# PCIe_UART_Bridge.net
KiCad netlist of a schematic drawn in Altium Designer
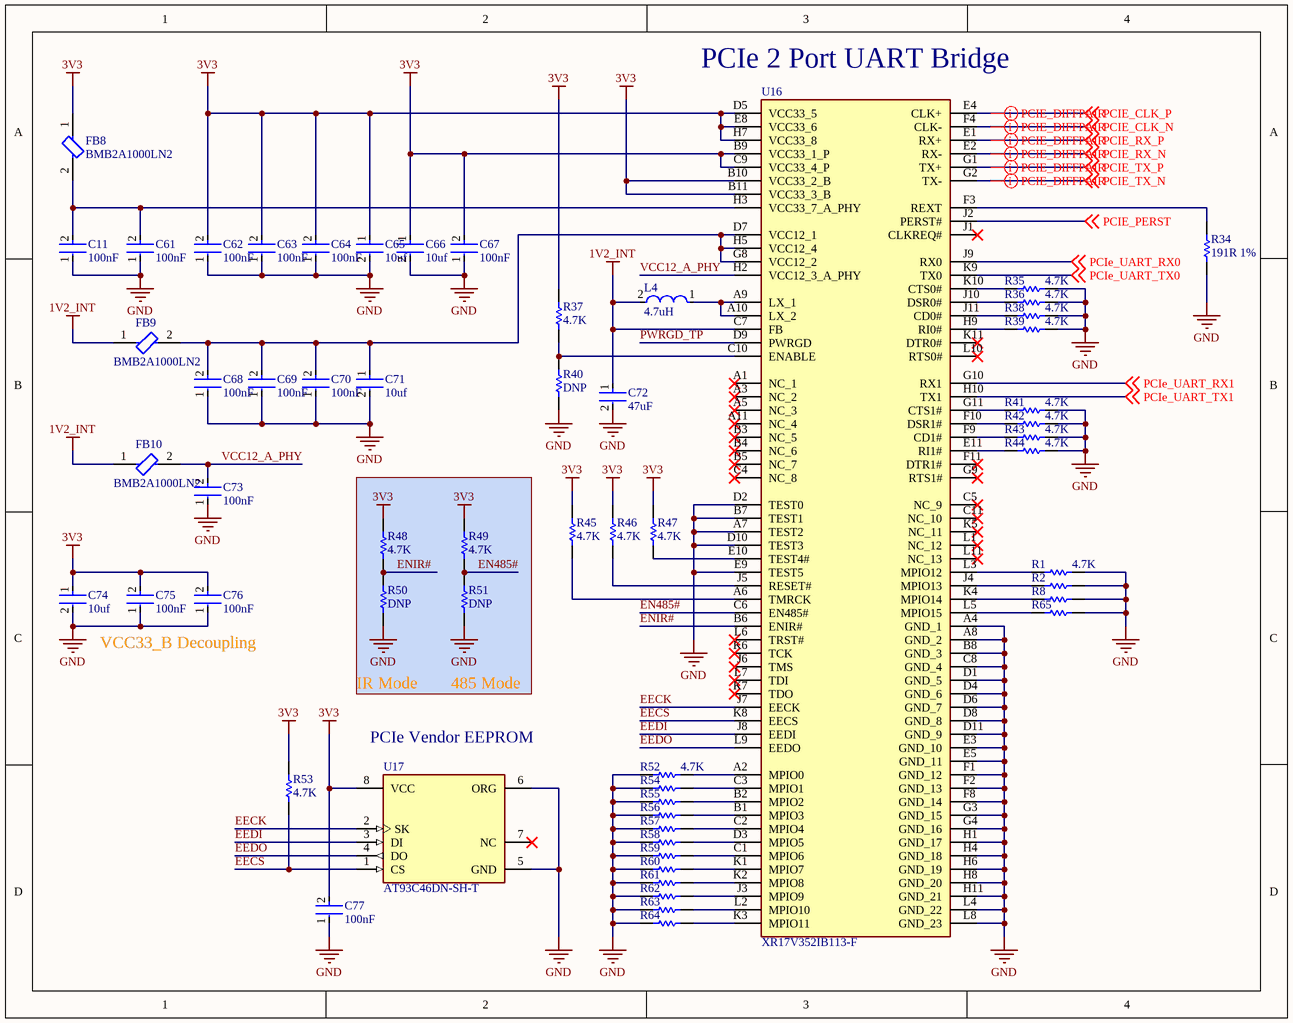
[diagram p0: PCIe_UART_Bridge.SchDoc]

(export (version "E")
  (design (tool "Eeschema 10.0.6"))
  (components
    (comp (ref "C11")
      (value "100nF")
      (footprint "FP-GRM15-MFG")
      (description "CAP CER 0.1UF 16V X7R 0402")
      (fields (field (name "MANUFACTURER PART NUMBER") "GRM155R71C104KA88D") (field (name "TOLERANCE") "10%"))
      (libsource (lib "Altium Content Vault") (part "236180d848d6139a670b325ea6854c9"))
    )
    (comp (ref "C61")
      (value "100nF")
      (footprint "FP-GRM15-MFG")
      (description "CAP CER 0.1UF 16V X7R 0402")
      (fields (field (name "MANUFACTURER PART NUMBER") "GRM155R71C104KA88D") (field (name "TOLERANCE") "10%"))
      (libsource (lib "Altium Content Vault") (part "236180d848d6139a670b325ea6854c9"))
    )
    (comp (ref "C62")
      (value "100nF")
      (footprint "FP-GRM15-MFG")
      (description "CAP CER 0.1UF 16V X7R 0402")
      (fields (field (name "MANUFACTURER PART NUMBER") "GRM155R71C104KA88D") (field (name "TOLERANCE") "10%"))
      (libsource (lib "Altium Content Vault") (part "236180d848d6139a670b325ea6854c9"))
    )
    (comp (ref "C63")
      (value "100nF")
      (footprint "FP-GRM15-MFG")
      (description "CAP CER 0.1UF 16V X7R 0402")
      (fields (field (name "MANUFACTURER PART NUMBER") "GRM155R71C104KA88D") (field (name "TOLERANCE") "10%"))
      (libsource (lib "Altium Content Vault") (part "236180d848d6139a670b325ea6854c9"))
    )
    (comp (ref "C64")
      (value "100nF")
      (footprint "FP-GRM15-MFG")
      (description "CAP CER 0.1UF 16V X7R 0402")
      (fields (field (name "MANUFACTURER PART NUMBER") "GRM155R71C104KA88D") (field (name "TOLERANCE") "10%"))
      (libsource (lib "Altium Content Vault") (part "236180d848d6139a670b325ea6854c9"))
    )
    (comp (ref "C65")
      (value "10uf")
      (footprint "FP-GRM188-0_2-IPC_C")
      (description "Chip Multilayer Ceramic Capacitors for General Purpose, 0603, 10uF, X5R, 15%, 20%, 35V")
      (fields (field (name "TOLERANCE") "20%"))
      (libsource (lib "Altium Content Vault") (part "11868f565c42a9108669ba33697ecf6"))
    )
    (comp (ref "C66")
      (value "10uf")
      (footprint "FP-GRM188-0_2-IPC_C")
      (description "Chip Multilayer Ceramic Capacitors for General Purpose, 0603, 10uF, X5R, 15%, 20%, 35V")
      (fields (field (name "TOLERANCE") "20%"))
      (libsource (lib "Altium Content Vault") (part "11868f565c42a9108669ba33697ecf6"))
    )
    (comp (ref "C67")
      (value "100nF")
      (footprint "FP-GRM15-MFG")
      (description "CAP CER 0.1UF 16V X7R 0402")
      (fields (field (name "MANUFACTURER PART NUMBER") "GRM155R71C104KA88D") (field (name "TOLERANCE") "10%"))
      (libsource (lib "Altium Content Vault") (part "236180d848d6139a670b325ea6854c9"))
    )
    (comp (ref "C68")
      (value "100nF")
      (footprint "FP-GRM15-MFG")
      (description "CAP CER 0.1UF 16V X7R 0402")
      (fields (field (name "MANUFACTURER PART NUMBER") "GRM155R71C104KA88D") (field (name "TOLERANCE") "10%"))
      (libsource (lib "Altium Content Vault") (part "236180d848d6139a670b325ea6854c9"))
    )
    (comp (ref "C69")
      (value "100nF")
      (footprint "FP-GRM15-MFG")
      (description "CAP CER 0.1UF 16V X7R 0402")
      (fields (field (name "MANUFACTURER PART NUMBER") "GRM155R71C104KA88D") (field (name "TOLERANCE") "10%"))
      (libsource (lib "Altium Content Vault") (part "236180d848d6139a670b325ea6854c9"))
    )
    (comp (ref "C70")
      (value "100nF")
      (footprint "FP-GRM15-MFG")
      (description "CAP CER 0.1UF 16V X7R 0402")
      (fields (field (name "MANUFACTURER PART NUMBER") "GRM155R71C104KA88D") (field (name "TOLERANCE") "10%"))
      (libsource (lib "Altium Content Vault") (part "236180d848d6139a670b325ea6854c9"))
    )
    (comp (ref "C71")
      (value "10uf")
      (footprint "FP-GRM188-0_2-IPC_C")
      (description "Chip Multilayer Ceramic Capacitors for General Purpose, 0603, 10uF, X5R, 15%, 20%, 35V")
      (fields (field (name "TOLERANCE") "20%"))
      (libsource (lib "Altium Content Vault") (part "11868f565c42a9108669ba33697ecf6"))
    )
    (comp (ref "C72")
      (value "47uF")
      (footprint "FP-C2012-125-0_2-IPC_B")
      (description "Multilayer Ceramic Capacitors 47μF ±20% 10V X5R SMD 0805")
      (fields (field (name "VOLTAGE") "10V") (field (name "TOLERANCE") "20%"))
      (libsource (lib "Altium Content Vault") (part "b4654b650e69147ec39a6b967a45e02"))
    )
    (comp (ref "C73")
      (value "100nF")
      (footprint "FP-GRM15-MFG")
      (description "CAP CER 0.1UF 16V X7R 0402")
      (fields (field (name "MANUFACTURER PART NUMBER") "GRM155R71C104KA88D") (field (name "TOLERANCE") "10%"))
      (libsource (lib "Altium Content Vault") (part "236180d848d6139a670b325ea6854c9"))
    )
    (comp (ref "C74")
      (value "10uf")
      (footprint "FP-GRM188-0_2-IPC_C")
      (description "Chip Multilayer Ceramic Capacitors for General Purpose, 0603, 10uF, X5R, 15%, 20%, 35V")
      (fields (field (name "TOLERANCE") "20%"))
      (libsource (lib "Altium Content Vault") (part "11868f565c42a9108669ba33697ecf6"))
    )
    (comp (ref "C75")
      (value "100nF")
      (footprint "FP-GRM15-MFG")
      (description "CAP CER 0.1UF 16V X7R 0402")
      (fields (field (name "MANUFACTURER PART NUMBER") "GRM155R71C104KA88D") (field (name "TOLERANCE") "10%"))
      (libsource (lib "Altium Content Vault") (part "236180d848d6139a670b325ea6854c9"))
    )
    (comp (ref "C76")
      (value "100nF")
      (footprint "FP-GRM15-MFG")
      (description "CAP CER 0.1UF 16V X7R 0402")
      (fields (field (name "MANUFACTURER PART NUMBER") "GRM155R71C104KA88D") (field (name "TOLERANCE") "10%"))
      (libsource (lib "Altium Content Vault") (part "236180d848d6139a670b325ea6854c9"))
    )
    (comp (ref "C77")
      (value "100nF")
      (footprint "FP-GRM15-MFG")
      (description "CAP CER 0.1UF 16V X7R 0402")
      (fields (field (name "MANUFACTURER PART NUMBER") "GRM155R71C104KA88D") (field (name "TOLERANCE") "10%"))
      (libsource (lib "Altium Content Vault") (part "236180d848d6139a670b325ea6854c9"))
    )
    (comp (ref "FB8")
      (value "BMB2A1000LN2")
      (footprint "FP-BMB2A1000LN2-IPC_C")
      (description "FERRITE BEAD 1 KOHM 0805 1LN")
      (fields (field (name "TOLERANCE") "25%"))
      (libsource (lib "Altium Content Vault") (part "5f30dd21d616792df468990f7003faa"))
    )
    (comp (ref "FB9")
      (value "BMB2A1000LN2")
      (footprint "FP-BMB2A1000LN2-IPC_C")
      (description "FERRITE BEAD 1 KOHM 0805 1LN")
      (fields (field (name "TOLERANCE") "25%"))
      (libsource (lib "Altium Content Vault") (part "5f30dd21d616792df468990f7003faa"))
    )
    (comp (ref "FB10")
      (value "BMB2A1000LN2")
      (footprint "FP-BMB2A1000LN2-IPC_C")
      (description "FERRITE BEAD 1 KOHM 0805 1LN")
      (fields (field (name "TOLERANCE") "25%"))
      (libsource (lib "Altium Content Vault") (part "5f30dd21d616792df468990f7003faa"))
    )
    (comp (ref "L4")
      (value "4.7uH")
      (footprint "FP-NR3012-MFG")
      (description "SMD Power Inductors 4.7uH ±20% 0.77A 0.13Ω")
      (fields (field (name "TOLERANCE") "20%"))
      (libsource (lib "Altium Content Vault") (part "725321dda6339637d4d059423bc1c3c"))
    )
    (comp (ref "R1")
      (value "4.7K")
      (footprint "RESC1005X40X25LL05T05")
      (description "Chip Resistor, 4.7 KOhm, +/- 1%, 0.1 W, -55 to 155 degC, 0402 (1005 Metric), RoHS, Tape and Reel")
      (fields (field (name "TOLERANCE") "1%") (field (name "PARTNUMBER") "ERJ-2RKF4701X"))
      (libsource (lib "Altium Content Vault") (part "RES-2"))
    )
    (comp (ref "R2")
      (value "4.7K")
      (footprint "RESC1005X40X25LL05T05")
      (description "Chip Resistor, 4.7 KOhm, +/- 1%, 0.1 W, -55 to 155 degC, 0402 (1005 Metric), RoHS, Tape and Reel")
      (fields (field (name "TOLERANCE") "1%") (field (name "PARTNUMBER") "ERJ-2RKF4701X"))
      (libsource (lib "Altium Content Vault") (part "RES-2"))
    )
    (comp (ref "R8")
      (value "4.7K")
      (footprint "RESC1005X40X25LL05T05")
      (description "Chip Resistor, 4.7 KOhm, +/- 1%, 0.1 W, -55 to 155 degC, 0402 (1005 Metric), RoHS, Tape and Reel")
      (fields (field (name "TOLERANCE") "1%") (field (name "PARTNUMBER") "ERJ-2RKF4701X"))
      (libsource (lib "Altium Content Vault") (part "RES-2"))
    )
    (comp (ref "R34")
      (value "191R 1%")
      (footprint "RESC1005X40X25ML05T05")
      (fields (field (name "MANUFACTURER") "Panasonic") (field (name "PART NUMBER") "ERJ-2RKF1910X"))
      (libsource (lib "Altium Content Vault") (part "RES"))
    )
    (comp (ref "R35")
      (value "4.7K")
      (footprint "RESC1005X40X25LL05T05")
      (description "Chip Resistor, 4.7 KOhm, +/- 1%, 0.1 W, -55 to 155 degC, 0402 (1005 Metric), RoHS, Tape and Reel")
      (fields (field (name "TOLERANCE") "1%") (field (name "PARTNUMBER") "ERJ-2RKF4701X"))
      (libsource (lib "Altium Content Vault") (part "RES-2"))
    )
    (comp (ref "R36")
      (value "4.7K")
      (footprint "RESC1005X40X25LL05T05")
      (description "Chip Resistor, 4.7 KOhm, +/- 1%, 0.1 W, -55 to 155 degC, 0402 (1005 Metric), RoHS, Tape and Reel")
      (fields (field (name "TOLERANCE") "1%") (field (name "PARTNUMBER") "ERJ-2RKF4701X"))
      (libsource (lib "Altium Content Vault") (part "RES-2"))
    )
    (comp (ref "R37")
      (value "4.7K")
      (footprint "RESC1005X40X25LL05T05")
      (description "Chip Resistor, 4.7 KOhm, +/- 1%, 0.1 W, -55 to 155 degC, 0402 (1005 Metric), RoHS, Tape and Reel")
      (fields (field (name "TOLERANCE") "1%") (field (name "PARTNUMBER") "ERJ-2RKF4701X"))
      (libsource (lib "Altium Content Vault") (part "RES-2"))
    )
    (comp (ref "R38")
      (value "4.7K")
      (footprint "RESC1005X40X25LL05T05")
      (description "Chip Resistor, 4.7 KOhm, +/- 1%, 0.1 W, -55 to 155 degC, 0402 (1005 Metric), RoHS, Tape and Reel")
      (fields (field (name "TOLERANCE") "1%") (field (name "PARTNUMBER") "ERJ-2RKF4701X"))
      (libsource (lib "Altium Content Vault") (part "RES-2"))
    )
    (comp (ref "R39")
      (value "4.7K")
      (footprint "RESC1005X40X25LL05T05")
      (description "Chip Resistor, 4.7 KOhm, +/- 1%, 0.1 W, -55 to 155 degC, 0402 (1005 Metric), RoHS, Tape and Reel")
      (fields (field (name "TOLERANCE") "1%") (field (name "PARTNUMBER") "ERJ-2RKF4701X"))
      (libsource (lib "Altium Content Vault") (part "RES-2"))
    )
    (comp (ref "R40")
      (value "DNP")
      (footprint "RESC1005X40X25LL05T05")
      (fields (field (name "TOLERANCE") "1%") (field (name "PARTNUMBER") "ERJ-2RKF4701X"))
      (libsource (lib "Altium Content Vault") (part "RES-2"))
    )
    (comp (ref "R41")
      (value "4.7K")
      (footprint "RESC1005X40X25LL05T05")
      (description "Chip Resistor, 4.7 KOhm, +/- 1%, 0.1 W, -55 to 155 degC, 0402 (1005 Metric), RoHS, Tape and Reel")
      (fields (field (name "TOLERANCE") "1%") (field (name "PARTNUMBER") "ERJ-2RKF4701X"))
      (libsource (lib "Altium Content Vault") (part "RES-2"))
    )
    (comp (ref "R42")
      (value "4.7K")
      (footprint "RESC1005X40X25LL05T05")
      (description "Chip Resistor, 4.7 KOhm, +/- 1%, 0.1 W, -55 to 155 degC, 0402 (1005 Metric), RoHS, Tape and Reel")
      (fields (field (name "TOLERANCE") "1%") (field (name "PARTNUMBER") "ERJ-2RKF4701X"))
      (libsource (lib "Altium Content Vault") (part "RES-2"))
    )
    (comp (ref "R43")
      (value "4.7K")
      (footprint "RESC1005X40X25LL05T05")
      (description "Chip Resistor, 4.7 KOhm, +/- 1%, 0.1 W, -55 to 155 degC, 0402 (1005 Metric), RoHS, Tape and Reel")
      (fields (field (name "TOLERANCE") "1%") (field (name "PARTNUMBER") "ERJ-2RKF4701X"))
      (libsource (lib "Altium Content Vault") (part "RES-2"))
    )
    (comp (ref "R44")
      (value "4.7K")
      (footprint "RESC1005X40X25LL05T05")
      (description "Chip Resistor, 4.7 KOhm, +/- 1%, 0.1 W, -55 to 155 degC, 0402 (1005 Metric), RoHS, Tape and Reel")
      (fields (field (name "TOLERANCE") "1%") (field (name "PARTNUMBER") "ERJ-2RKF4701X"))
      (libsource (lib "Altium Content Vault") (part "RES-2"))
    )
    (comp (ref "R45")
      (value "4.7K")
      (footprint "RESC1005X40X25LL05T05")
      (description "Chip Resistor, 4.7 KOhm, +/- 1%, 0.1 W, -55 to 155 degC, 0402 (1005 Metric), RoHS, Tape and Reel")
      (fields (field (name "TOLERANCE") "1%") (field (name "PARTNUMBER") "ERJ-2RKF4701X"))
      (libsource (lib "Altium Content Vault") (part "RES-2"))
    )
    (comp (ref "R46")
      (value "4.7K")
      (footprint "RESC1005X40X25LL05T05")
      (description "Chip Resistor, 4.7 KOhm, +/- 1%, 0.1 W, -55 to 155 degC, 0402 (1005 Metric), RoHS, Tape and Reel")
      (fields (field (name "TOLERANCE") "1%") (field (name "PARTNUMBER") "ERJ-2RKF4701X"))
      (libsource (lib "Altium Content Vault") (part "RES-2"))
    )
    (comp (ref "R47")
      (value "4.7K")
      (footprint "RESC1005X40X25LL05T05")
      (description "Chip Resistor, 4.7 KOhm, +/- 1%, 0.1 W, -55 to 155 degC, 0402 (1005 Metric), RoHS, Tape and Reel")
      (fields (field (name "TOLERANCE") "1%") (field (name "PARTNUMBER") "ERJ-2RKF4701X"))
      (libsource (lib "Altium Content Vault") (part "RES-2"))
    )
    (comp (ref "R48")
      (value "4.7K")
      (footprint "RESC1005X40X25LL05T05")
      (description "Chip Resistor, 4.7 KOhm, +/- 1%, 0.1 W, -55 to 155 degC, 0402 (1005 Metric), RoHS, Tape and Reel")
      (fields (field (name "TOLERANCE") "1%") (field (name "PARTNUMBER") "ERJ-2RKF4701X"))
      (libsource (lib "Altium Content Vault") (part "RES-2"))
    )
    (comp (ref "R49")
      (value "4.7K")
      (footprint "RESC1005X40X25LL05T05")
      (description "Chip Resistor, 4.7 KOhm, +/- 1%, 0.1 W, -55 to 155 degC, 0402 (1005 Metric), RoHS, Tape and Reel")
      (fields (field (name "TOLERANCE") "1%") (field (name "PARTNUMBER") "ERJ-2RKF4701X"))
      (libsource (lib "Altium Content Vault") (part "RES-2"))
    )
    (comp (ref "R50")
      (value "DNP")
      (footprint "RESC1005X40X25LL05T05")
      (description "Chip Resistor, 4.7 KOhm, +/- 1%, 0.1 W, -55 to 155 degC, 0402 (1005 Metric), RoHS, Tape and Reel")
      (fields (field (name "TOLERANCE") "1%") (field (name "PARTNUMBER") "ERJ-2RKF4701X"))
      (libsource (lib "Altium Content Vault") (part "RES-2"))
    )
    (comp (ref "R51")
      (value "DNP")
      (footprint "RESC1005X40X25LL05T05")
      (description "Chip Resistor, 4.7 KOhm, +/- 1%, 0.1 W, -55 to 155 degC, 0402 (1005 Metric), RoHS, Tape and Reel")
      (fields (field (name "TOLERANCE") "1%") (field (name "PARTNUMBER") "ERJ-2RKF4701X"))
      (libsource (lib "Altium Content Vault") (part "RES-2"))
    )
    (comp (ref "R52")
      (value "4.7K")
      (footprint "RESC1005X40X25LL05T05")
      (description "Chip Resistor, 4.7 KOhm, +/- 1%, 0.1 W, -55 to 155 degC, 0402 (1005 Metric), RoHS, Tape and Reel")
      (fields (field (name "TOLERANCE") "1%") (field (name "PARTNUMBER") "ERJ-2RKF4701X"))
      (libsource (lib "Altium Content Vault") (part "RES-2"))
    )
    (comp (ref "R53")
      (value "4.7K")
      (footprint "RESC1005X40X25LL05T05")
      (description "Chip Resistor, 4.7 KOhm, +/- 1%, 0.1 W, -55 to 155 degC, 0402 (1005 Metric), RoHS, Tape and Reel")
      (fields (field (name "TOLERANCE") "1%") (field (name "PARTNUMBER") "ERJ-2RKF4701X"))
      (libsource (lib "Altium Content Vault") (part "RES-2"))
    )
    (comp (ref "R54")
      (value "4.7K")
      (footprint "RESC1005X40X25LL05T05")
      (description "Chip Resistor, 4.7 KOhm, +/- 1%, 0.1 W, -55 to 155 degC, 0402 (1005 Metric), RoHS, Tape and Reel")
      (fields (field (name "TOLERANCE") "1%") (field (name "PARTNUMBER") "ERJ-2RKF4701X"))
      (libsource (lib "Altium Content Vault") (part "RES-2"))
    )
    (comp (ref "R55")
      (value "4.7K")
      (footprint "RESC1005X40X25LL05T05")
      (description "Chip Resistor, 4.7 KOhm, +/- 1%, 0.1 W, -55 to 155 degC, 0402 (1005 Metric), RoHS, Tape and Reel")
      (fields (field (name "TOLERANCE") "1%") (field (name "PARTNUMBER") "ERJ-2RKF4701X"))
      (libsource (lib "Altium Content Vault") (part "RES-2"))
    )
    (comp (ref "R56")
      (value "4.7K")
      (footprint "RESC1005X40X25LL05T05")
      (description "Chip Resistor, 4.7 KOhm, +/- 1%, 0.1 W, -55 to 155 degC, 0402 (1005 Metric), RoHS, Tape and Reel")
      (fields (field (name "TOLERANCE") "1%") (field (name "PARTNUMBER") "ERJ-2RKF4701X"))
      (libsource (lib "Altium Content Vault") (part "RES-2"))
    )
    (comp (ref "R57")
      (value "4.7K")
      (footprint "RESC1005X40X25LL05T05")
      (description "Chip Resistor, 4.7 KOhm, +/- 1%, 0.1 W, -55 to 155 degC, 0402 (1005 Metric), RoHS, Tape and Reel")
      (fields (field (name "TOLERANCE") "1%") (field (name "PARTNUMBER") "ERJ-2RKF4701X"))
      (libsource (lib "Altium Content Vault") (part "RES-2"))
    )
    (comp (ref "R58")
      (value "4.7K")
      (footprint "RESC1005X40X25LL05T05")
      (description "Chip Resistor, 4.7 KOhm, +/- 1%, 0.1 W, -55 to 155 degC, 0402 (1005 Metric), RoHS, Tape and Reel")
      (fields (field (name "TOLERANCE") "1%") (field (name "PARTNUMBER") "ERJ-2RKF4701X"))
      (libsource (lib "Altium Content Vault") (part "RES-2"))
    )
    (comp (ref "R59")
      (value "4.7K")
      (footprint "RESC1005X40X25LL05T05")
      (description "Chip Resistor, 4.7 KOhm, +/- 1%, 0.1 W, -55 to 155 degC, 0402 (1005 Metric), RoHS, Tape and Reel")
      (fields (field (name "TOLERANCE") "1%") (field (name "PARTNUMBER") "ERJ-2RKF4701X"))
      (libsource (lib "Altium Content Vault") (part "RES-2"))
    )
    (comp (ref "R60")
      (value "4.7K")
      (footprint "RESC1005X40X25LL05T05")
      (description "Chip Resistor, 4.7 KOhm, +/- 1%, 0.1 W, -55 to 155 degC, 0402 (1005 Metric), RoHS, Tape and Reel")
      (fields (field (name "TOLERANCE") "1%") (field (name "PARTNUMBER") "ERJ-2RKF4701X"))
      (libsource (lib "Altium Content Vault") (part "RES-2"))
    )
    (comp (ref "R61")
      (value "4.7K")
      (footprint "RESC1005X40X25LL05T05")
      (description "Chip Resistor, 4.7 KOhm, +/- 1%, 0.1 W, -55 to 155 degC, 0402 (1005 Metric), RoHS, Tape and Reel")
      (fields (field (name "TOLERANCE") "1%") (field (name "PARTNUMBER") "ERJ-2RKF4701X"))
      (libsource (lib "Altium Content Vault") (part "RES-2"))
    )
    (comp (ref "R62")
      (value "4.7K")
      (footprint "RESC1005X40X25LL05T05")
      (description "Chip Resistor, 4.7 KOhm, +/- 1%, 0.1 W, -55 to 155 degC, 0402 (1005 Metric), RoHS, Tape and Reel")
      (fields (field (name "TOLERANCE") "1%") (field (name "PARTNUMBER") "ERJ-2RKF4701X"))
      (libsource (lib "Altium Content Vault") (part "RES-2"))
    )
    (comp (ref "R63")
      (value "4.7K")
      (footprint "RESC1005X40X25LL05T05")
      (description "Chip Resistor, 4.7 KOhm, +/- 1%, 0.1 W, -55 to 155 degC, 0402 (1005 Metric), RoHS, Tape and Reel")
      (fields (field (name "TOLERANCE") "1%") (field (name "PARTNUMBER") "ERJ-2RKF4701X"))
      (libsource (lib "Altium Content Vault") (part "RES-2"))
    )
    (comp (ref "R64")
      (value "4.7K")
      (footprint "RESC1005X40X25LL05T05")
      (description "Chip Resistor, 4.7 KOhm, +/- 1%, 0.1 W, -55 to 155 degC, 0402 (1005 Metric), RoHS, Tape and Reel")
      (fields (field (name "TOLERANCE") "1%") (field (name "PARTNUMBER") "ERJ-2RKF4701X"))
      (libsource (lib "Altium Content Vault") (part "RES-2"))
    )
    (comp (ref "R65")
      (value "4.7K")
      (footprint "RESC1005X40X25LL05T05")
      (description "Chip Resistor, 4.7 KOhm, +/- 1%, 0.1 W, -55 to 155 degC, 0402 (1005 Metric), RoHS, Tape and Reel")
      (fields (field (name "TOLERANCE") "1%") (field (name "PARTNUMBER") "ERJ-2RKF4701X"))
      (libsource (lib "Altium Content Vault") (part "RES-2"))
    )
    (comp (ref "U16")
      (value "XR17V352IB113-F")
      (footprint "SamacSys:BGA113C80P11X11_900X900X153")
      (description "Integrated Circuit")
      (fields (field (name "MOUSER PART NUMBER") "701-XR17V352IB113-F"))
      (libsource (lib "SamacSys") (part "XR17V352IB113-F"))
    )
    (comp (ref "U17")
      (value "AT93C46DN-SH-T")
      (footprint "FP-C04-057-SN-MFG")
      (description "IC EEPROM 1K SPI 2MHZ 8SOIC")
      (fields
        (field (name "MANUFACTURER") "Microchip")
        (field (name "OCTOPART") "https://octopart.com/at93c46dn-sh-t-microchip-77759177")
      )
      (libsource (lib "Altium Content Vault") (part "8bb9afc094b350e480db350c7247e52"))
    )
  )
  (nets
    (net (code "1") (name "/EECK") (class "Default")
      (node (ref "U16") (pin "J7") (pinfunction "EECK_J7") (pintype "passive"))
      (node (ref "U17") (pin "2") (pinfunction "SK_2") (pintype "input"))
    )
    (net (code "2") (name "/EECS") (class "Default")
      (node (ref "R53") (pin "1") (pinfunction "1_1") (pintype "passive"))
      (node (ref "U16") (pin "K8") (pinfunction "EECS_K8") (pintype "passive"))
      (node (ref "U17") (pin "1") (pinfunction "CS_1") (pintype "input"))
    )
    (net (code "3") (name "/EEDI") (class "Default")
      (node (ref "U16") (pin "J8") (pinfunction "EEDI_J8") (pintype "passive"))
      (node (ref "U17") (pin "3") (pinfunction "DI_3") (pintype "input"))
    )
    (net (code "4") (name "/EEDO") (class "Default")
      (node (ref "U16") (pin "L9") (pinfunction "EEDO_L9") (pintype "passive"))
      (node (ref "U17") (pin "4") (pinfunction "DO_4") (pintype "output"))
    )
    (net (code "5") (name "/EN485#") (class "Default")
      (node (ref "R49") (pin "1") (pinfunction "1_1") (pintype "passive"))
      (node (ref "R51") (pin "2") (pinfunction "2_2") (pintype "passive"))
      (node (ref "U16") (pin "C6") (pinfunction "EN485#_C6") (pintype "passive"))
    )
    (net (code "6") (name "/ENIR#") (class "Default")
      (node (ref "R48") (pin "1") (pinfunction "1_1") (pintype "passive"))
      (node (ref "R50") (pin "2") (pinfunction "2_2") (pintype "passive"))
      (node (ref "U16") (pin "B6") (pinfunction "ENIR#_B6") (pintype "passive"))
    )
    (net (code "7") (name "/PWRGD_TP") (class "Default")
      (node (ref "U16") (pin "D9") (pinfunction "PWRGD_D9") (pintype "passive"))
    )
    (net (code "8") (name "/VCC12_A_PHY") (class "Default")
      (node (ref "C73") (pin "2") (pinfunction "2_2") (pintype "passive"))
      (node (ref "FB10") (pin "2") (pinfunction "2_2") (pintype "passive"))
      (node (ref "U16") (pin "H2") (pinfunction "VCC12_3_A_PHY_H2") (pintype "passive"))
    )
    (net (code "9") (name "1V2_INT") (class "Default")
      (node (ref "C72") (pin "1") (pinfunction "1_1") (pintype "passive"))
      (node (ref "FB10") (pin "1") (pinfunction "1_1") (pintype "passive"))
      (node (ref "FB9") (pin "1") (pinfunction "1_1") (pintype "passive"))
      (node (ref "L4") (pin "2") (pinfunction "2_2") (pintype "passive"))
      (node (ref "U16") (pin "C7") (pinfunction "FB_C7") (pintype "passive"))
    )
    (net (code "10") (name "3V3") (class "Default")
      (node (ref "C62") (pin "2") (pinfunction "2_2") (pintype "passive"))
      (node (ref "C63") (pin "2") (pinfunction "2_2") (pintype "passive"))
      (node (ref "C64") (pin "2") (pinfunction "2_2") (pintype "passive"))
      (node (ref "C65") (pin "1") (pinfunction "1_1") (pintype "passive"))
      (node (ref "C66") (pin "1") (pinfunction "1_1") (pintype "passive"))
      (node (ref "C67") (pin "2") (pinfunction "2_2") (pintype "passive"))
      (node (ref "C74") (pin "1") (pinfunction "1_1") (pintype "passive"))
      (node (ref "C75") (pin "2") (pinfunction "2_2") (pintype "passive"))
      (node (ref "C76") (pin "2") (pinfunction "2_2") (pintype "passive"))
      (node (ref "C77") (pin "2") (pinfunction "2_2") (pintype "passive"))
      (node (ref "FB8") (pin "1") (pinfunction "1_1") (pintype "passive"))
      (node (ref "R37") (pin "2") (pinfunction "2_2") (pintype "passive"))
      (node (ref "R45") (pin "2") (pinfunction "2_2") (pintype "passive"))
      (node (ref "R46") (pin "2") (pinfunction "2_2") (pintype "passive"))
      (node (ref "R47") (pin "2") (pinfunction "2_2") (pintype "passive"))
      (node (ref "R48") (pin "2") (pinfunction "2_2") (pintype "passive"))
      (node (ref "R49") (pin "2") (pinfunction "2_2") (pintype "passive"))
      (node (ref "R53") (pin "2") (pinfunction "2_2") (pintype "passive"))
      (node (ref "U16") (pin "B10") (pinfunction "VCC33_2_B_B10") (pintype "passive"))
      (node (ref "U16") (pin "B11") (pinfunction "VCC33_3_B_B11") (pintype "passive"))
      (node (ref "U16") (pin "B9") (pinfunction "VCC33_1_P_B9") (pintype "passive"))
      (node (ref "U16") (pin "C9") (pinfunction "VCC33_4_P_C9") (pintype "passive"))
      (node (ref "U16") (pin "D5") (pinfunction "VCC33_5_D5") (pintype "passive"))
      (node (ref "U16") (pin "E8") (pinfunction "VCC33_6_E8") (pintype "passive"))
      (node (ref "U16") (pin "H7") (pinfunction "VCC33_8_H7") (pintype "passive"))
      (node (ref "U17") (pin "8") (pinfunction "VCC_8") (pintype "power_in"))
    )
    (net (code "11") (name "GND") (class "Default")
      (node (ref "C11") (pin "1") (pinfunction "1_1") (pintype "passive"))
      (node (ref "C61") (pin "1") (pinfunction "1_1") (pintype "passive"))
      (node (ref "C62") (pin "1") (pinfunction "1_1") (pintype "passive"))
      (node (ref "C63") (pin "1") (pinfunction "1_1") (pintype "passive"))
      (node (ref "C64") (pin "1") (pinfunction "1_1") (pintype "passive"))
      (node (ref "C65") (pin "2") (pinfunction "2_2") (pintype "passive"))
      (node (ref "C66") (pin "2") (pinfunction "2_2") (pintype "passive"))
      (node (ref "C67") (pin "1") (pinfunction "1_1") (pintype "passive"))
      (node (ref "C68") (pin "1") (pinfunction "1_1") (pintype "passive"))
      (node (ref "C69") (pin "1") (pinfunction "1_1") (pintype "passive"))
      (node (ref "C70") (pin "1") (pinfunction "1_1") (pintype "passive"))
      (node (ref "C71") (pin "2") (pinfunction "2_2") (pintype "passive"))
      (node (ref "C72") (pin "2") (pinfunction "2_2") (pintype "passive"))
      (node (ref "C73") (pin "1") (pinfunction "1_1") (pintype "passive"))
      (node (ref "C74") (pin "2") (pinfunction "2_2") (pintype "passive"))
      (node (ref "C75") (pin "1") (pinfunction "1_1") (pintype "passive"))
      (node (ref "C76") (pin "1") (pinfunction "1_1") (pintype "passive"))
      (node (ref "C77") (pin "1") (pinfunction "1_1") (pintype "passive"))
      (node (ref "R1") (pin "1") (pinfunction "1_1") (pintype "passive"))
      (node (ref "R2") (pin "1") (pinfunction "1_1") (pintype "passive"))
      (node (ref "R34") (pin "2") (pinfunction "2_2") (pintype "passive"))
      (node (ref "R35") (pin "1") (pinfunction "1_1") (pintype "passive"))
      (node (ref "R36") (pin "1") (pinfunction "1_1") (pintype "passive"))
      (node (ref "R38") (pin "1") (pinfunction "1_1") (pintype "passive"))
      (node (ref "R39") (pin "1") (pinfunction "1_1") (pintype "passive"))
      (node (ref "R40") (pin "1") (pinfunction "1_1") (pintype "passive"))
      (node (ref "R41") (pin "1") (pinfunction "1_1") (pintype "passive"))
      (node (ref "R42") (pin "1") (pinfunction "1_1") (pintype "passive"))
      (node (ref "R43") (pin "1") (pinfunction "1_1") (pintype "passive"))
      (node (ref "R44") (pin "1") (pinfunction "1_1") (pintype "passive"))
      (node (ref "R50") (pin "1") (pinfunction "1_1") (pintype "passive"))
      (node (ref "R51") (pin "1") (pinfunction "1_1") (pintype "passive"))
      (node (ref "R52") (pin "2") (pinfunction "2_2") (pintype "passive"))
      (node (ref "R54") (pin "2") (pinfunction "2_2") (pintype "passive"))
      (node (ref "R55") (pin "2") (pinfunction "2_2") (pintype "passive"))
      (node (ref "R56") (pin "2") (pinfunction "2_2") (pintype "passive"))
      (node (ref "R57") (pin "2") (pinfunction "2_2") (pintype "passive"))
      (node (ref "R58") (pin "2") (pinfunction "2_2") (pintype "passive"))
      (node (ref "R59") (pin "2") (pinfunction "2_2") (pintype "passive"))
      (node (ref "R60") (pin "2") (pinfunction "2_2") (pintype "passive"))
      (node (ref "R61") (pin "2") (pinfunction "2_2") (pintype "passive"))
      (node (ref "R62") (pin "2") (pinfunction "2_2") (pintype "passive"))
      (node (ref "R63") (pin "2") (pinfunction "2_2") (pintype "passive"))
      (node (ref "R64") (pin "2") (pinfunction "2_2") (pintype "passive"))
      (node (ref "R65") (pin "1") (pinfunction "1_1") (pintype "passive"))
      (node (ref "R8") (pin "1") (pinfunction "1_1") (pintype "passive"))
      (node (ref "U16") (pin "A4") (pinfunction "GND_1_A4") (pintype "passive"))
      (node (ref "U16") (pin "A7") (pinfunction "TEST2_A7") (pintype "passive"))
      (node (ref "U16") (pin "A8") (pinfunction "GND_2_A8") (pintype "passive"))
      (node (ref "U16") (pin "B7") (pinfunction "TEST1_B7") (pintype "passive"))
      (node (ref "U16") (pin "B8") (pinfunction "GND_3_B8") (pintype "passive"))
      (node (ref "U16") (pin "C8") (pinfunction "GND_4_C8") (pintype "passive"))
      (node (ref "U16") (pin "D1") (pinfunction "GND_5_D1") (pintype "passive"))
      (node (ref "U16") (pin "D10") (pinfunction "TEST3_D10") (pintype "passive"))
      (node (ref "U16") (pin "D11") (pinfunction "GND_9_D11") (pintype "passive"))
      (node (ref "U16") (pin "D2") (pinfunction "TEST0_D2") (pintype "passive"))
      (node (ref "U16") (pin "D4") (pinfunction "GND_6_D4") (pintype "passive"))
      (node (ref "U16") (pin "D6") (pinfunction "GND_7_D6") (pintype "passive"))
      (node (ref "U16") (pin "D8") (pinfunction "GND_8_D8") (pintype "passive"))
      (node (ref "U16") (pin "E3") (pinfunction "GND_10_E3") (pintype "passive"))
      (node (ref "U16") (pin "E5") (pinfunction "GND_11_E5") (pintype "passive"))
      (node (ref "U16") (pin "E9") (pinfunction "TEST5_E9") (pintype "passive"))
      (node (ref "U16") (pin "F1") (pinfunction "GND_12_F1") (pintype "passive"))
      (node (ref "U16") (pin "F2") (pinfunction "GND_13_F2") (pintype "passive"))
      (node (ref "U16") (pin "F8") (pinfunction "GND_14_F8") (pintype "passive"))
      (node (ref "U16") (pin "G3") (pinfunction "GND_15_G3") (pintype "passive"))
      (node (ref "U16") (pin "G4") (pinfunction "GND_16_G4") (pintype "passive"))
      (node (ref "U16") (pin "H1") (pinfunction "GND_17_H1") (pintype "passive"))
      (node (ref "U16") (pin "H11") (pinfunction "GND_21_H11") (pintype "passive"))
      (node (ref "U16") (pin "H4") (pinfunction "GND_18_H4") (pintype "passive"))
      (node (ref "U16") (pin "H6") (pinfunction "GND_19_H6") (pintype "passive"))
      (node (ref "U16") (pin "H8") (pinfunction "GND_20_H8") (pintype "passive"))
      (node (ref "U16") (pin "L4") (pinfunction "GND_22_L4") (pintype "passive"))
      (node (ref "U16") (pin "L8") (pinfunction "GND_23_L8") (pintype "passive"))
      (node (ref "U17") (pin "5") (pinfunction "GND_5") (pintype "power_in"))
      (node (ref "U17") (pin "6") (pinfunction "ORG_6") (pintype "passive"))
    )
    (net (code "12") (name "Net-(U16-CD0#)") (class "Default")
      (node (ref "R38") (pin "2") (pinfunction "2_2") (pintype "passive"))
      (node (ref "U16") (pin "J11") (pinfunction "CD0#_J11") (pintype "passive"))
    )
    (net (code "13") (name "Net-(U16-CD1#)") (class "Default")
      (node (ref "R43") (pin "2") (pinfunction "2_2") (pintype "passive"))
      (node (ref "U16") (pin "F9") (pinfunction "CD1#_F9") (pintype "passive"))
    )
    (net (code "14") (name "Net-(U16-CTS0#)") (class "Default")
      (node (ref "R35") (pin "2") (pinfunction "2_2") (pintype "passive"))
      (node (ref "U16") (pin "K10") (pinfunction "CTS0#_K10") (pintype "passive"))
    )
    (net (code "15") (name "Net-(U16-CTS1#)") (class "Default")
      (node (ref "R41") (pin "2") (pinfunction "2_2") (pintype "passive"))
      (node (ref "U16") (pin "G11") (pinfunction "CTS1#_G11") (pintype "passive"))
    )
    (net (code "16") (name "Net-(U16-DSR0#)") (class "Default")
      (node (ref "R36") (pin "2") (pinfunction "2_2") (pintype "passive"))
      (node (ref "U16") (pin "J10") (pinfunction "DSR0#_J10") (pintype "passive"))
    )
    (net (code "17") (name "Net-(U16-DSR1#)") (class "Default")
      (node (ref "R42") (pin "2") (pinfunction "2_2") (pintype "passive"))
      (node (ref "U16") (pin "F10") (pinfunction "DSR1#_F10") (pintype "passive"))
    )
    (net (code "18") (name "Net-(U16-ENABLE)") (class "Default")
      (node (ref "R37") (pin "1") (pinfunction "1_1") (pintype "passive"))
      (node (ref "R40") (pin "2") (pinfunction "2_2") (pintype "passive"))
      (node (ref "U16") (pin "C10") (pinfunction "ENABLE_C10") (pintype "passive"))
    )
    (net (code "19") (name "Net-(U16-LX_1)") (class "Default")
      (node (ref "L4") (pin "1") (pinfunction "1_1") (pintype "passive"))
      (node (ref "U16") (pin "A10") (pinfunction "LX_2_A10") (pintype "passive"))
      (node (ref "U16") (pin "A9") (pinfunction "LX_1_A9") (pintype "passive"))
    )
    (net (code "20") (name "Net-(U16-MPIO0)") (class "Default")
      (node (ref "R52") (pin "1") (pinfunction "1_1") (pintype "passive"))
      (node (ref "U16") (pin "A2") (pinfunction "MPIO0_A2") (pintype "passive"))
    )
    (net (code "21") (name "Net-(U16-MPIO1)") (class "Default")
      (node (ref "R54") (pin "1") (pinfunction "1_1") (pintype "passive"))
      (node (ref "U16") (pin "C3") (pinfunction "MPIO1_C3") (pintype "passive"))
    )
    (net (code "22") (name "Net-(U16-MPIO2)") (class "Default")
      (node (ref "R55") (pin "1") (pinfunction "1_1") (pintype "passive"))
      (node (ref "U16") (pin "B2") (pinfunction "MPIO2_B2") (pintype "passive"))
    )
    (net (code "23") (name "Net-(U16-MPIO3)") (class "Default")
      (node (ref "R56") (pin "1") (pinfunction "1_1") (pintype "passive"))
      (node (ref "U16") (pin "B1") (pinfunction "MPIO3_B1") (pintype "passive"))
    )
    (net (code "24") (name "Net-(U16-MPIO4)") (class "Default")
      (node (ref "R57") (pin "1") (pinfunction "1_1") (pintype "passive"))
      (node (ref "U16") (pin "C2") (pinfunction "MPIO4_C2") (pintype "passive"))
    )
    (net (code "25") (name "Net-(U16-MPIO5)") (class "Default")
      (node (ref "R58") (pin "1") (pinfunction "1_1") (pintype "passive"))
      (node (ref "U16") (pin "D3") (pinfunction "MPIO5_D3") (pintype "passive"))
    )
    (net (code "26") (name "Net-(U16-MPIO6)") (class "Default")
      (node (ref "R59") (pin "1") (pinfunction "1_1") (pintype "passive"))
      (node (ref "U16") (pin "C1") (pinfunction "MPIO6_C1") (pintype "passive"))
    )
    (net (code "27") (name "Net-(U16-MPIO7)") (class "Default")
      (node (ref "R60") (pin "1") (pinfunction "1_1") (pintype "passive"))
      (node (ref "U16") (pin "K1") (pinfunction "MPIO7_K1") (pintype "passive"))
    )
    (net (code "28") (name "Net-(U16-MPIO8)") (class "Default")
      (node (ref "R61") (pin "1") (pinfunction "1_1") (pintype "passive"))
      (node (ref "U16") (pin "K2") (pinfunction "MPIO8_K2") (pintype "passive"))
    )
    (net (code "29") (name "Net-(U16-MPIO9)") (class "Default")
      (node (ref "R62") (pin "1") (pinfunction "1_1") (pintype "passive"))
      (node (ref "U16") (pin "J3") (pinfunction "MPIO9_J3") (pintype "passive"))
    )
    (net (code "30") (name "Net-(U16-MPIO10)") (class "Default")
      (node (ref "R63") (pin "1") (pinfunction "1_1") (pintype "passive"))
      (node (ref "U16") (pin "L2") (pinfunction "MPIO10_L2") (pintype "passive"))
    )
    (net (code "31") (name "Net-(U16-MPIO11)") (class "Default")
      (node (ref "R64") (pin "1") (pinfunction "1_1") (pintype "passive"))
      (node (ref "U16") (pin "K3") (pinfunction "MPIO11_K3") (pintype "passive"))
    )
    (net (code "32") (name "Net-(U16-MPIO12)") (class "Default")
      (node (ref "R1") (pin "2") (pinfunction "2_2") (pintype "passive"))
      (node (ref "U16") (pin "L3") (pinfunction "MPIO12_L3") (pintype "passive"))
    )
    (net (code "33") (name "Net-(U16-MPIO13)") (class "Default")
      (node (ref "R2") (pin "2") (pinfunction "2_2") (pintype "passive"))
      (node (ref "U16") (pin "J4") (pinfunction "MPIO13_J4") (pintype "passive"))
    )
    (net (code "34") (name "Net-(U16-MPIO14)") (class "Default")
      (node (ref "R8") (pin "2") (pinfunction "2_2") (pintype "passive"))
      (node (ref "U16") (pin "K4") (pinfunction "MPIO14_K4") (pintype "passive"))
    )
    (net (code "35") (name "Net-(U16-MPIO15)") (class "Default")
      (node (ref "R65") (pin "2") (pinfunction "2_2") (pintype "passive"))
      (node (ref "U16") (pin "L5") (pinfunction "MPIO15_L5") (pintype "passive"))
    )
    (net (code "36") (name "Net-(U16-RESET#)") (class "Default")
      (node (ref "R46") (pin "1") (pinfunction "1_1") (pintype "passive"))
      (node (ref "U16") (pin "J5") (pinfunction "RESET#_J5") (pintype "passive"))
    )
    (net (code "37") (name "Net-(U16-REXT)") (class "Default")
      (node (ref "R34") (pin "1") (pinfunction "1_1") (pintype "passive"))
      (node (ref "U16") (pin "F3") (pinfunction "REXT_F3") (pintype "passive"))
    )
    (net (code "38") (name "Net-(U16-RI0#)") (class "Default")
      (node (ref "R39") (pin "2") (pinfunction "2_2") (pintype "passive"))
      (node (ref "U16") (pin "H9") (pinfunction "RI0#_H9") (pintype "passive"))
    )
    (net (code "39") (name "Net-(U16-RI1#)") (class "Default")
      (node (ref "R44") (pin "2") (pinfunction "2_2") (pintype "passive"))
      (node (ref "U16") (pin "E11") (pinfunction "RI1#_E11") (pintype "passive"))
    )
    (net (code "40") (name "Net-(U16-TEST4#)") (class "Default")
      (node (ref "R47") (pin "1") (pinfunction "1_1") (pintype "passive"))
      (node (ref "U16") (pin "E10") (pinfunction "TEST4#_E10") (pintype "passive"))
    )
    (net (code "41") (name "Net-(U16-TMRCK)") (class "Default")
      (node (ref "R45") (pin "1") (pinfunction "1_1") (pintype "passive"))
      (node (ref "U16") (pin "A6") (pinfunction "TMRCK_A6") (pintype "passive"))
    )
    (net (code "42") (name "Net-(U16-VCC12_1)") (class "Default")
      (node (ref "C68") (pin "2") (pinfunction "2_2") (pintype "passive"))
      (node (ref "C69") (pin "2") (pinfunction "2_2") (pintype "passive"))
      (node (ref "C70") (pin "2") (pinfunction "2_2") (pintype "passive"))
      (node (ref "C71") (pin "1") (pinfunction "1_1") (pintype "passive"))
      (node (ref "FB9") (pin "2") (pinfunction "2_2") (pintype "passive"))
      (node (ref "U16") (pin "D7") (pinfunction "VCC12_1_D7") (pintype "passive"))
      (node (ref "U16") (pin "G8") (pinfunction "VCC12_2_G8") (pintype "passive"))
      (node (ref "U16") (pin "H5") (pinfunction "VCC12_4_H5") (pintype "passive"))
    )
    (net (code "43") (name "Net-(U16-VCC33_7_A_PHY)") (class "Default")
      (node (ref "C11") (pin "2") (pinfunction "2_2") (pintype "passive"))
      (node (ref "C61") (pin "2") (pinfunction "2_2") (pintype "passive"))
      (node (ref "FB8") (pin "2") (pinfunction "2_2") (pintype "passive"))
      (node (ref "U16") (pin "H3") (pinfunction "VCC33_7_A_PHY_H3") (pintype "passive"))
    )
    (net (code "44") (name "PCIE_CLK_N") (class "Default")
      (node (ref "U16") (pin "F4") (pinfunction "CLK-_F4") (pintype "passive"))
    )
    (net (code "45") (name "PCIE_CLK_P") (class "Default")
      (node (ref "U16") (pin "E4") (pinfunction "CLK+_E4") (pintype "passive"))
    )
    (net (code "46") (name "PCIE_PERST") (class "Default")
      (node (ref "U16") (pin "J2") (pinfunction "PERST#_J2") (pintype "passive"))
    )
    (net (code "47") (name "PCIE_RX_N") (class "Default")
      (node (ref "U16") (pin "E2") (pinfunction "RX-_E2") (pintype "passive"))
    )
    (net (code "48") (name "PCIE_RX_P") (class "Default")
      (node (ref "U16") (pin "E1") (pinfunction "RX+_E1") (pintype "passive"))
    )
    (net (code "49") (name "PCIE_TX_N") (class "Default")
      (node (ref "U16") (pin "G2") (pinfunction "TX-_G2") (pintype "passive"))
    )
    (net (code "50") (name "PCIE_TX_P") (class "Default")
      (node (ref "U16") (pin "G1") (pinfunction "TX+_G1") (pintype "passive"))
    )
    (net (code "51") (name "PCIe_UART_RX0") (class "Default")
      (node (ref "U16") (pin "J9") (pinfunction "RX0_J9") (pintype "passive"))
    )
    (net (code "52") (name "PCIe_UART_RX1") (class "Default")
      (node (ref "U16") (pin "G10") (pinfunction "RX1_G10") (pintype "passive"))
    )
    (net (code "53") (name "PCIe_UART_TX0") (class "Default")
      (node (ref "U16") (pin "K9") (pinfunction "TX0_K9") (pintype "passive"))
    )
    (net (code "54") (name "PCIe_UART_TX1") (class "Default")
      (node (ref "U16") (pin "H10") (pinfunction "TX1_H10") (pintype "passive"))
    )
    (net (code "55") (name "unconnected-(U16-CLKREQ#-PadJ1)") (class "Default")
      (node (ref "U16") (pin "J1") (pinfunction "CLKREQ#_J1") (pintype "passive+no_connect"))
    )
    (net (code "56") (name "unconnected-(U16-DTR0#-PadK11)") (class "Default")
      (node (ref "U16") (pin "K11") (pinfunction "DTR0#_K11") (pintype "passive+no_connect"))
    )
    (net (code "57") (name "unconnected-(U16-DTR1#-PadF11)") (class "Default")
      (node (ref "U16") (pin "F11") (pinfunction "DTR1#_F11") (pintype "passive+no_connect"))
    )
    (net (code "58") (name "unconnected-(U16-NC_1-PadA1)") (class "Default")
      (node (ref "U16") (pin "A1") (pinfunction "NC_1_A1") (pintype "passive+no_connect"))
    )
    (net (code "59") (name "unconnected-(U16-NC_2-PadA3)") (class "Default")
      (node (ref "U16") (pin "A3") (pinfunction "NC_2_A3") (pintype "passive+no_connect"))
    )
    (net (code "60") (name "unconnected-(U16-NC_3-PadA5)") (class "Default")
      (node (ref "U16") (pin "A5") (pinfunction "NC_3_A5") (pintype "passive+no_connect"))
    )
    (net (code "61") (name "unconnected-(U16-NC_4-PadA11)") (class "Default")
      (node (ref "U16") (pin "A11") (pinfunction "NC_4_A11") (pintype "passive+no_connect"))
    )
    (net (code "62") (name "unconnected-(U16-NC_5-PadB3)") (class "Default")
      (node (ref "U16") (pin "B3") (pinfunction "NC_5_B3") (pintype "passive+no_connect"))
    )
    (net (code "63") (name "unconnected-(U16-NC_6-PadB4)") (class "Default")
      (node (ref "U16") (pin "B4") (pinfunction "NC_6_B4") (pintype "passive+no_connect"))
    )
    (net (code "64") (name "unconnected-(U16-NC_7-PadB5)") (class "Default")
      (node (ref "U16") (pin "B5") (pinfunction "NC_7_B5") (pintype "passive+no_connect"))
    )
    (net (code "65") (name "unconnected-(U16-NC_8-PadC4)") (class "Default")
      (node (ref "U16") (pin "C4") (pinfunction "NC_8_C4") (pintype "passive+no_connect"))
    )
    (net (code "66") (name "unconnected-(U16-NC_9-PadC5)") (class "Default")
      (node (ref "U16") (pin "C5") (pinfunction "NC_9_C5") (pintype "passive+no_connect"))
    )
    (net (code "67") (name "unconnected-(U16-NC_10-PadC11)") (class "Default")
      (node (ref "U16") (pin "C11") (pinfunction "NC_10_C11") (pintype "passive+no_connect"))
    )
    (net (code "68") (name "unconnected-(U16-NC_11-PadK5)") (class "Default")
      (node (ref "U16") (pin "K5") (pinfunction "NC_11_K5") (pintype "passive+no_connect"))
    )
    (net (code "69") (name "unconnected-(U16-NC_12-PadL1)") (class "Default")
      (node (ref "U16") (pin "L1") (pinfunction "NC_12_L1") (pintype "passive+no_connect"))
    )
    (net (code "70") (name "unconnected-(U16-NC_13-PadL11)") (class "Default")
      (node (ref "U16") (pin "L11") (pinfunction "NC_13_L11") (pintype "passive+no_connect"))
    )
    (net (code "71") (name "unconnected-(U16-RTS0#-PadL10)") (class "Default")
      (node (ref "U16") (pin "L10") (pinfunction "RTS0#_L10") (pintype "passive+no_connect"))
    )
    (net (code "72") (name "unconnected-(U16-RTS1#-PadG9)") (class "Default")
      (node (ref "U16") (pin "G9") (pinfunction "RTS1#_G9") (pintype "passive+no_connect"))
    )
    (net (code "73") (name "unconnected-(U16-TCK-PadK6)") (class "Default")
      (node (ref "U16") (pin "K6") (pinfunction "TCK_K6") (pintype "passive+no_connect"))
    )
    (net (code "74") (name "unconnected-(U16-TDI-PadL7)") (class "Default")
      (node (ref "U16") (pin "L7") (pinfunction "TDI_L7") (pintype "passive+no_connect"))
    )
    (net (code "75") (name "unconnected-(U16-TDO-PadK7)") (class "Default")
      (node (ref "U16") (pin "K7") (pinfunction "TDO_K7") (pintype "passive+no_connect"))
    )
    (net (code "76") (name "unconnected-(U16-TMS-PadJ6)") (class "Default")
      (node (ref "U16") (pin "J6") (pinfunction "TMS_J6") (pintype "passive+no_connect"))
    )
    (net (code "77") (name "unconnected-(U16-TRST#-PadL6)") (class "Default")
      (node (ref "U16") (pin "L6") (pinfunction "TRST#_L6") (pintype "passive+no_connect"))
    )
    (net (code "78") (name "unconnected-(U17-NC-Pad7)") (class "Default")
      (node (ref "U17") (pin "7") (pinfunction "NC_7") (pintype "passive+no_connect"))
    )
  )
)
